# LEDboard_v0_4-R001.net
KiCad netlist of a schematic drawn in EAGLE
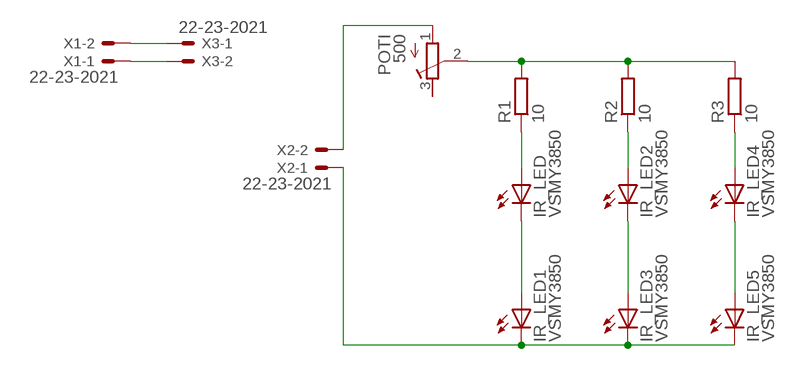
[diagram p0: schematic, sheet 1]

(export (version "E")
  (design (tool "Eeschema 10.0.6"))
  (components
    (comp (ref "IR_LED")
      (value "VSMY3850")
      (footprint "eagle-import:VSMY3850X")
      (libsource (lib "eagle-import") (part "VSMY3850"))
    )
    (comp (ref "IR_LED1")
      (value "VSMY3850")
      (footprint "eagle-import:VSMY3850X")
      (libsource (lib "eagle-import") (part "VSMY3850"))
    )
    (comp (ref "IR_LED2")
      (value "VSMY3850")
      (footprint "eagle-import:VSMY3850X")
      (libsource (lib "eagle-import") (part "VSMY3850"))
    )
    (comp (ref "IR_LED3")
      (value "VSMY3850")
      (footprint "eagle-import:VSMY3850X")
      (libsource (lib "eagle-import") (part "VSMY3850"))
    )
    (comp (ref "IR_LED4")
      (value "VSMY3850")
      (footprint "eagle-import:VSMY3850X")
      (libsource (lib "eagle-import") (part "VSMY3850"))
    )
    (comp (ref "IR_LED5")
      (value "VSMY3850")
      (footprint "eagle-import:VSMY3850X")
      (libsource (lib "eagle-import") (part "VSMY3850"))
    )
    (comp (ref "POTI")
      (value "500")
      (footprint "eagle-import:RTRIM64Y")
      (libsource (lib "eagle-import") (part "R-TRIMM64Y"))
    )
    (comp (ref "R1")
      (value "10")
      (footprint "eagle-import:R0805")
      (libsource (lib "eagle-import") (part "R-EU_R0805"))
    )
    (comp (ref "R2")
      (value "10")
      (footprint "eagle-import:R0805")
      (libsource (lib "eagle-import") (part "R-EU_R0805"))
    )
    (comp (ref "R3")
      (value "10")
      (footprint "eagle-import:R0805")
      (libsource (lib "eagle-import") (part "R-EU_R0805"))
    )
    (comp (ref "X1")
      (value "22-23-2021")
      (footprint "eagle-import:22-23-2021")
      (fields (field (name "MF") "MOLEX"))
      (libsource (lib "eagle-import") (part "22-23-2021"))
    )
    (comp (ref "X2")
      (value "22-23-2021")
      (footprint "eagle-import:22-23-2021")
      (fields (field (name "MF") "MOLEX"))
      (libsource (lib "eagle-import") (part "22-23-2021"))
    )
    (comp (ref "X3")
      (value "22-23-2021")
      (footprint "eagle-import:22-23-2021")
      (fields (field (name "MF") "MOLEX"))
      (libsource (lib "eagle-import") (part "22-23-2021"))
    )
  )
  (nets
    (net (code "1") (name "Net-(IR_LED-A)") (class "Default")
      (node (ref "IR_LED") (pin "1") (pinfunction "A_1") (pintype "passive"))
      (node (ref "R1") (pin "1") (pinfunction "1_1") (pintype "passive"))
    )
    (net (code "2") (name "Net-(IR_LED-C)") (class "Default")
      (node (ref "IR_LED") (pin "2") (pinfunction "C_2") (pintype "passive"))
      (node (ref "IR_LED1") (pin "1") (pinfunction "A_1") (pintype "passive"))
    )
    (net (code "3") (name "Net-(IR_LED1-C)") (class "Default")
      (node (ref "IR_LED1") (pin "2") (pinfunction "C_2") (pintype "passive"))
      (node (ref "IR_LED3") (pin "2") (pinfunction "C_2") (pintype "passive"))
      (node (ref "IR_LED5") (pin "2") (pinfunction "C_2") (pintype "passive"))
      (node (ref "X2") (pin "1") (pinfunction "S_1") (pintype "passive"))
    )
    (net (code "4") (name "Net-(IR_LED2-A)") (class "Default")
      (node (ref "IR_LED2") (pin "1") (pinfunction "A_1") (pintype "passive"))
      (node (ref "R2") (pin "1") (pinfunction "1_1") (pintype "passive"))
    )
    (net (code "5") (name "Net-(IR_LED2-C)") (class "Default")
      (node (ref "IR_LED2") (pin "2") (pinfunction "C_2") (pintype "passive"))
      (node (ref "IR_LED3") (pin "1") (pinfunction "A_1") (pintype "passive"))
    )
    (net (code "6") (name "Net-(IR_LED4-A)") (class "Default")
      (node (ref "IR_LED4") (pin "1") (pinfunction "A_1") (pintype "passive"))
      (node (ref "R3") (pin "1") (pinfunction "1_1") (pintype "passive"))
    )
    (net (code "7") (name "Net-(IR_LED4-C)") (class "Default")
      (node (ref "IR_LED4") (pin "2") (pinfunction "C_2") (pintype "passive"))
      (node (ref "IR_LED5") (pin "1") (pinfunction "A_1") (pintype "passive"))
    )
    (net (code "8") (name "Net-(POTI-A)") (class "Default")
      (node (ref "POTI") (pin "1") (pinfunction "A_1") (pintype "passive"))
      (node (ref "X2") (pin "2") (pinfunction "S_2") (pintype "passive"))
    )
    (net (code "9") (name "Net-(POTI-S)") (class "Default")
      (node (ref "POTI") (pin "2") (pinfunction "S_2") (pintype "passive"))
      (node (ref "R1") (pin "2") (pinfunction "2_2") (pintype "passive"))
      (node (ref "R2") (pin "2") (pinfunction "2_2") (pintype "passive"))
      (node (ref "R3") (pin "2") (pinfunction "2_2") (pintype "passive"))
    )
    (net (code "10") (name "Net-(X1A-S)") (class "Default")
      (node (ref "X1") (pin "1") (pinfunction "S_1") (pintype "passive"))
      (node (ref "X3") (pin "2") (pinfunction "S_2") (pintype "passive"))
    )
    (net (code "11") (name "Net-(X1B-S)") (class "Default")
      (node (ref "X1") (pin "2") (pinfunction "S_2") (pintype "passive"))
      (node (ref "X3") (pin "1") (pinfunction "S_1") (pintype "passive"))
    )
    (net (code "12") (name "unconnected-(POTI-E-Pad3)") (class "Default")
      (node (ref "POTI") (pin "3") (pinfunction "E_3") (pintype "passive"))
    )
  )
)
